# 1-B.net
KiCad netlist of a schematic drawn in EAGLE
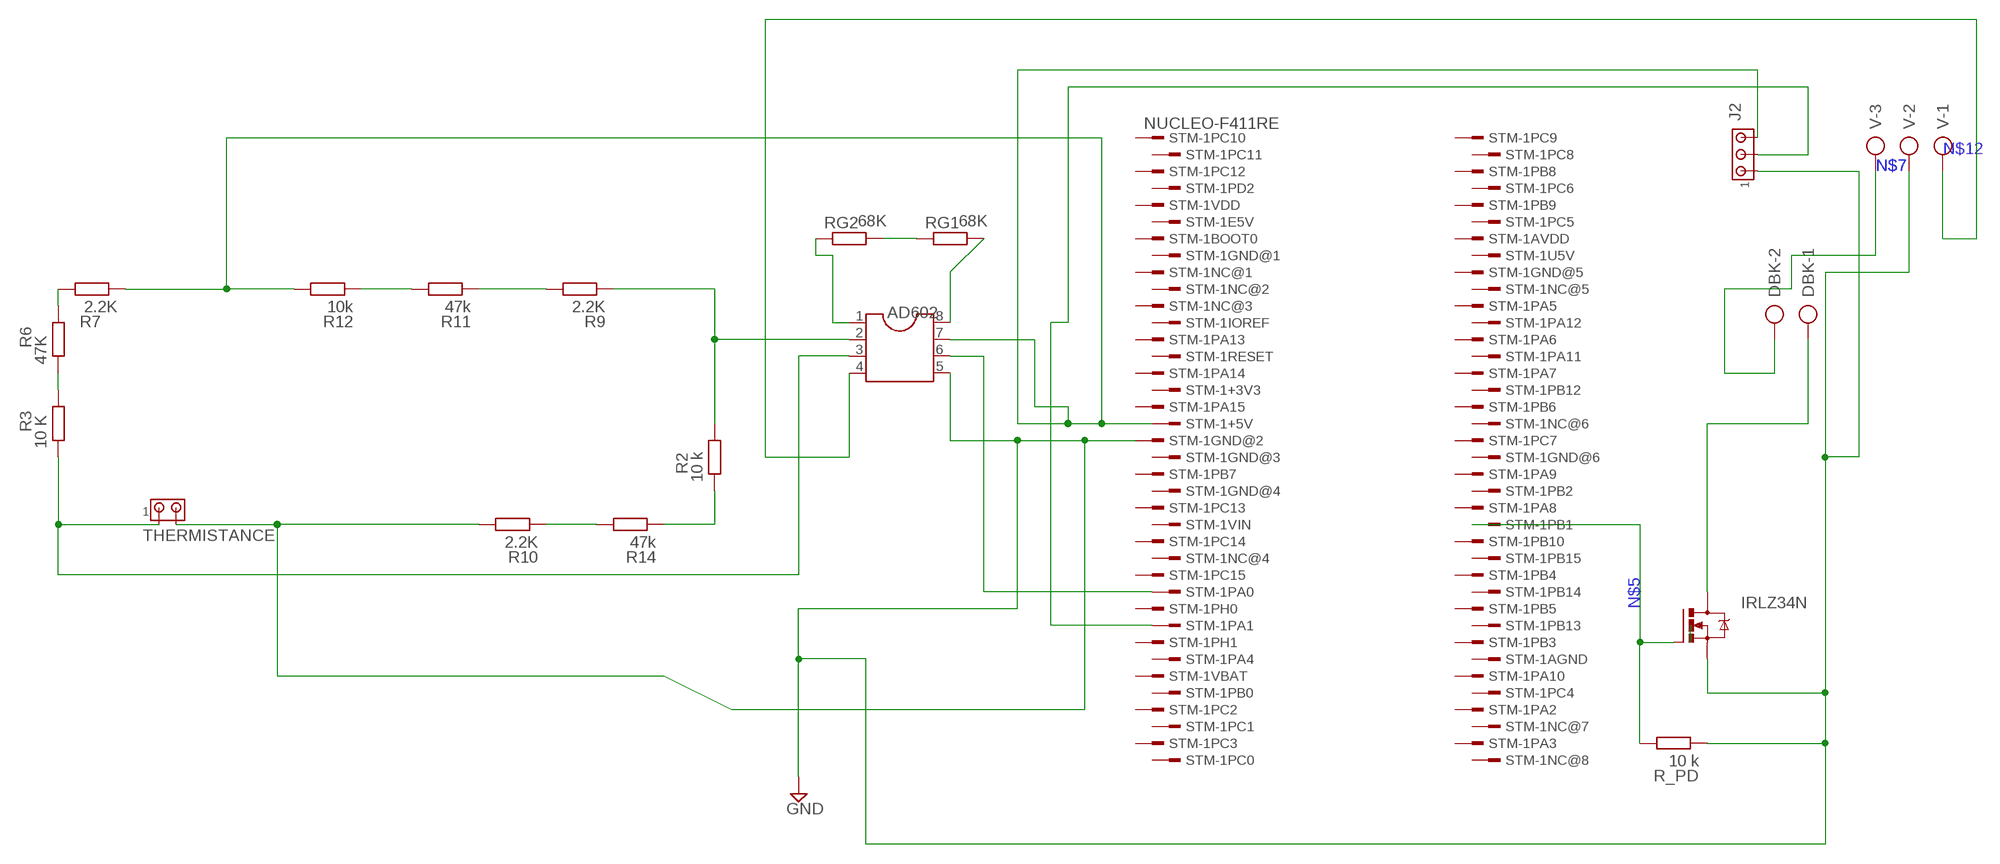
[diagram p0: schematic, sheet 1]

(export (version "E")
  (design (tool "Eeschema 10.0.6"))
  (components
    (comp (ref "AD602")
      (value "DIL8")
      (footprint "eagle-import:DIL08")
      (libsource (lib "eagle-import") (part "DIL8"))
    )
    (comp (ref "DBK")
      (value "AK500/2-H")
      (footprint "eagle-import:AK500_2-H")
      (libsource (lib "eagle-import") (part "AK500/2-H"))
    )
    (comp (ref "IRLZ34N")
      (value "IRLZ44Z")
      (footprint "eagle-import:TO220BH")
      (libsource (lib "eagle-import") (part "IRLZ44Z"))
    )
    (comp (ref "J2")
      (value "MTA03-100")
      (footprint "eagle-import:10X03MTA")
      (libsource (lib "eagle-import") (part "MTA03-100"))
    )
    (comp (ref "R2")
      (value "10 k")
      (footprint "eagle-import:0207_7")
      (libsource (lib "eagle-import") (part "R-EU_0207/7"))
    )
    (comp (ref "R3")
      (value "10 K")
      (footprint "eagle-import:0207_7")
      (libsource (lib "eagle-import") (part "R-EU_0207/7"))
    )
    (comp (ref "R6")
      (value "47K")
      (footprint "eagle-import:0207_7")
      (libsource (lib "eagle-import") (part "R-EU_0207/7"))
    )
    (comp (ref "R7")
      (value "2.2K")
      (footprint "eagle-import:0207_7")
      (libsource (lib "eagle-import") (part "R-EU_0207/7"))
    )
    (comp (ref "R9")
      (value "2.2K")
      (footprint "eagle-import:0207_7")
      (libsource (lib "eagle-import") (part "R-EU_0207/7"))
    )
    (comp (ref "R10")
      (value "2.2K")
      (footprint "eagle-import:0207_7")
      (libsource (lib "eagle-import") (part "R-EU_0207/7"))
    )
    (comp (ref "R11")
      (value "47k")
      (footprint "eagle-import:0207_7")
      (libsource (lib "eagle-import") (part "R-EU_0207/7"))
    )
    (comp (ref "R12")
      (value "10k")
      (footprint "eagle-import:0207_7")
      (libsource (lib "eagle-import") (part "R-EU_0207/7"))
    )
    (comp (ref "R14")
      (value "47k")
      (footprint "eagle-import:0207_7")
      (libsource (lib "eagle-import") (part "R-EU_0207/7"))
    )
    (comp (ref "RG1")
      (value "68K")
      (footprint "eagle-import:0207_7")
      (libsource (lib "eagle-import") (part "R-EU_0207/7"))
    )
    (comp (ref "RG2")
      (value "68K")
      (footprint "eagle-import:0207_7")
      (libsource (lib "eagle-import") (part "R-EU_0207/7"))
    )
    (comp (ref "R_PD")
      (value "10 k")
      (footprint "eagle-import:0207_7")
      (libsource (lib "eagle-import") (part "R-EU_0207/7"))
    )
    (comp (ref "STM-1")
      (value "NUCLEO-F411RE")
      (footprint "eagle-import:CONN_STM32_NUCLEO")
      (libsource (lib "eagle-import") (part "NUCLEO-F411RE"))
    )
    (comp (ref "THERMISTANCE")
      (value "MTA02-156")
      (footprint "eagle-import:1X2MTA")
      (libsource (lib "eagle-import") (part "MTA02-156"))
    )
    (comp (ref "V")
      (value "AK500/3-H")
      (footprint "eagle-import:AK500_3-H")
      (libsource (lib "eagle-import") (part "AK500/3-H"))
    )
  )
  (nets
    (net (code "1") (name "GND") (class "Default")
      (node (ref "AD602") (pin "5") (pinfunction "5_5") (pintype "passive"))
      (node (ref "IRLZ34N") (pin "S") (pinfunction "S_S") (pintype "passive"))
      (node (ref "J2") (pin "1") (pinfunction "1_1") (pintype "passive"))
      (node (ref "R10") (pin "2") (pinfunction "2_2") (pintype "passive"))
      (node (ref "R_PD") (pin "1") (pinfunction "1_1") (pintype "passive"))
      (node (ref "STM-1") (pin "19") (pinfunction "1_19") (pintype "passive"))
      (node (ref "THERMISTANCE") (pin "2") (pinfunction "2_2") (pintype "passive"))
      (node (ref "V") (pin "2") (pinfunction "KL_2") (pintype "passive"))
    )
    (net (code "2") (name "Net-(AD602-Pad1)") (class "Default")
      (node (ref "AD602") (pin "1") (pinfunction "1_1") (pintype "passive"))
      (node (ref "RG2") (pin "1") (pinfunction "1_1") (pintype "passive"))
    )
    (net (code "3") (name "Net-(AD602-Pad2)") (class "Default")
      (node (ref "AD602") (pin "2") (pinfunction "2_2") (pintype "passive"))
      (node (ref "R2") (pin "2") (pinfunction "2_2") (pintype "passive"))
      (node (ref "R9") (pin "1") (pinfunction "1_1") (pintype "passive"))
    )
    (net (code "4") (name "Net-(AD602-Pad3)") (class "Default")
      (node (ref "AD602") (pin "3") (pinfunction "3_3") (pintype "passive"))
      (node (ref "R3") (pin "1") (pinfunction "1_1") (pintype "passive"))
      (node (ref "THERMISTANCE") (pin "1") (pinfunction "1_1") (pintype "passive"))
    )
    (net (code "5") (name "Net-(AD602-Pad8)") (class "Default")
      (node (ref "AD602") (pin "8") (pinfunction "8_8") (pintype "passive"))
      (node (ref "RG1") (pin "2") (pinfunction "2_2") (pintype "passive"))
    )
    (net (code "6") (name "Net-(DBKA-KL)") (class "Default")
      (node (ref "DBK") (pin "1") (pinfunction "KL_1") (pintype "passive"))
      (node (ref "IRLZ34N") (pin "D") (pinfunction "D_D") (pintype "passive"))
    )
    (net (code "7") (name "Net-(DBKB-KL)") (class "Default")
      (node (ref "DBK") (pin "2") (pinfunction "KL_2") (pintype "passive"))
      (node (ref "V") (pin "3") (pinfunction "KL_3") (pintype "passive"))
    )
    (net (code "8") (name "Net-(R3-Pad2)") (class "Default")
      (node (ref "R3") (pin "2") (pinfunction "2_2") (pintype "passive"))
      (node (ref "R6") (pin "1") (pinfunction "1_1") (pintype "passive"))
    )
    (net (code "9") (name "Net-(R6-Pad2)") (class "Default")
      (node (ref "R6") (pin "2") (pinfunction "2_2") (pintype "passive"))
      (node (ref "R7") (pin "2") (pinfunction "2_2") (pintype "passive"))
    )
    (net (code "10") (name "Net-(R10-Pad1)") (class "Default")
      (node (ref "R10") (pin "1") (pinfunction "1_1") (pintype "passive"))
      (node (ref "R14") (pin "2") (pinfunction "2_2") (pintype "passive"))
    )
    (net (code "11") (name "Net-(R11-Pad1)") (class "Default")
      (node (ref "R11") (pin "1") (pinfunction "1_1") (pintype "passive"))
      (node (ref "R9") (pin "2") (pinfunction "2_2") (pintype "passive"))
    )
    (net (code "12") (name "Net-(R11-Pad2)") (class "Default")
      (node (ref "R11") (pin "2") (pinfunction "2_2") (pintype "passive"))
      (node (ref "R12") (pin "1") (pinfunction "1_1") (pintype "passive"))
    )
    (net (code "13") (name "Net-(R14-Pad1)") (class "Default")
      (node (ref "R14") (pin "1") (pinfunction "1_1") (pintype "passive"))
      (node (ref "R2") (pin "1") (pinfunction "1_1") (pintype "passive"))
    )
    (net (code "14") (name "Net-(RG1-Pad1)") (class "Default")
      (node (ref "RG1") (pin "1") (pinfunction "1_1") (pintype "passive"))
      (node (ref "RG2") (pin "2") (pinfunction "2_2") (pintype "passive"))
    )
    (net (code "15") (name "Net-(STM-1AM-1)") (class "Default")
      (node (ref "IRLZ34N") (pin "G") (pinfunction "G_G") (pintype "passive"))
      (node (ref "R_PD") (pin "2") (pinfunction "2_2") (pintype "passive"))
      (node (ref "STM-1") (pin "62") (pinfunction "1_62") (pintype "passive"))
    )
    (net (code "16") (name "Net-(STM-1B-1)") (class "Default")
      (node (ref "AD602") (pin "7") (pinfunction "7_7") (pintype "passive"))
      (node (ref "J2") (pin "3") (pinfunction "3_3") (pintype "passive"))
      (node (ref "R12") (pin "2") (pinfunction "2_2") (pintype "passive"))
      (node (ref "R7") (pin "1") (pinfunction "1_1") (pintype "passive"))
      (node (ref "STM-1") (pin "18") (pinfunction "1_18") (pintype "passive"))
    )
    (net (code "17") (name "Net-(STM-1V-1)") (class "Default")
      (node (ref "AD602") (pin "6") (pinfunction "6_6") (pintype "passive"))
      (node (ref "STM-1") (pin "28") (pinfunction "1_28") (pintype "passive"))
    )
    (net (code "18") (name "Net-(STM-1W-1)") (class "Default")
      (node (ref "J2") (pin "2") (pinfunction "2_2") (pintype "passive"))
      (node (ref "STM-1") (pin "30") (pinfunction "1_30") (pintype "passive"))
    )
    (net (code "19") (name "Net-(VA-KL)") (class "Default")
      (node (ref "AD602") (pin "4") (pinfunction "4_4") (pintype "passive"))
      (node (ref "V") (pin "1") (pinfunction "KL_1") (pintype "passive"))
    )
    (net (code "20") (name "unconnected-(STM-1-Pad1)") (class "Default")
      (node (ref "STM-1") (pin "1") (pinfunction "1_1") (pintype "passive"))
    )
    (net (code "21") (name "unconnected-(STM-1A-1-Pad16)") (class "Default")
      (node (ref "STM-1") (pin "16") (pinfunction "1_16") (pintype "passive"))
    )
    (net (code "22") (name "unconnected-(STM-1AA-1-Pad13)") (class "Default")
      (node (ref "STM-1") (pin "13") (pinfunction "1_13") (pintype "passive"))
    )
    (net (code "23") (name "unconnected-(STM-1AB-1-Pad15)") (class "Default")
      (node (ref "STM-1") (pin "15") (pinfunction "1_15") (pintype "passive"))
    )
    (net (code "24") (name "unconnected-(STM-1AC-1-Pad17)") (class "Default")
      (node (ref "STM-1") (pin "17") (pinfunction "1_17") (pintype "passive"))
    )
    (net (code "25") (name "unconnected-(STM-1AD-1-Pad73)") (class "Default")
      (node (ref "STM-1") (pin "73") (pinfunction "1_73") (pintype "passive"))
    )
    (net (code "26") (name "unconnected-(STM-1AE-1-Pad75)") (class "Default")
      (node (ref "STM-1") (pin "75") (pinfunction "1_75") (pintype "passive"))
    )
    (net (code "27") (name "unconnected-(STM-1AF-1-Pad32)") (class "Default")
      (node (ref "STM-1") (pin "32") (pinfunction "1_32") (pintype "passive"))
    )
    (net (code "28") (name "unconnected-(STM-1AG-1-Pad49)") (class "Default")
      (node (ref "STM-1") (pin "49") (pinfunction "1_49") (pintype "passive"))
    )
    (net (code "29") (name "unconnected-(STM-1AH-1-Pad51)") (class "Default")
      (node (ref "STM-1") (pin "51") (pinfunction "1_51") (pintype "passive"))
    )
    (net (code "30") (name "unconnected-(STM-1AI-1-Pad53)") (class "Default")
      (node (ref "STM-1") (pin "53") (pinfunction "1_53") (pintype "passive"))
    )
    (net (code "31") (name "unconnected-(STM-1AJ-1-Pad61)") (class "Default")
      (node (ref "STM-1") (pin "61") (pinfunction "1_61") (pintype "passive"))
    )
    (net (code "32") (name "unconnected-(STM-1AK-1-Pad59)") (class "Default")
      (node (ref "STM-1") (pin "59") (pinfunction "1_59") (pintype "passive"))
    )
    (net (code "33") (name "unconnected-(STM-1AL-1-Pad34)") (class "Default")
      (node (ref "STM-1") (pin "34") (pinfunction "1_34") (pintype "passive"))
    )
    (net (code "34") (name "unconnected-(STM-1AN-1-Pad63)") (class "Default")
      (node (ref "STM-1") (pin "63") (pinfunction "1_63") (pintype "passive"))
    )
    (net (code "35") (name "unconnected-(STM-1AO-1-Pad54)") (class "Default")
      (node (ref "STM-1") (pin "54") (pinfunction "1_54") (pintype "passive"))
    )
    (net (code "36") (name "unconnected-(STM-1AP-1-Pad68)") (class "Default")
      (node (ref "STM-1") (pin "68") (pinfunction "1_68") (pintype "passive"))
    )
    (net (code "37") (name "unconnected-(STM-1AQ-1-Pad66)") (class "Default")
      (node (ref "STM-1") (pin "66") (pinfunction "1_66") (pintype "passive"))
    )
    (net (code "38") (name "unconnected-(STM-1AR-1-Pad64)") (class "Default")
      (node (ref "STM-1") (pin "64") (pinfunction "1_64") (pintype "passive"))
    )
    (net (code "39") (name "unconnected-(STM-1AS-1-Pad60)") (class "Default")
      (node (ref "STM-1") (pin "60") (pinfunction "1_60") (pintype "passive"))
    )
    (net (code "40") (name "unconnected-(STM-1AT-1-Pad69)") (class "Default")
      (node (ref "STM-1") (pin "69") (pinfunction "1_69") (pintype "passive"))
    )
    (net (code "41") (name "unconnected-(STM-1AU-1-Pad65)") (class "Default")
      (node (ref "STM-1") (pin "65") (pinfunction "1_65") (pintype "passive"))
    )
    (net (code "42") (name "unconnected-(STM-1AV-1-Pad67)") (class "Default")
      (node (ref "STM-1") (pin "67") (pinfunction "1_67") (pintype "passive"))
    )
    (net (code "43") (name "unconnected-(STM-1AW-1-Pad55)") (class "Default")
      (node (ref "STM-1") (pin "55") (pinfunction "1_55") (pintype "passive"))
    )
    (net (code "44") (name "unconnected-(STM-1AX-1-Pad21)") (class "Default")
      (node (ref "STM-1") (pin "21") (pinfunction "1_21") (pintype "passive"))
    )
    (net (code "45") (name "unconnected-(STM-1AY-1-Pad41)") (class "Default")
      (node (ref "STM-1") (pin "41") (pinfunction "1_41") (pintype "passive"))
    )
    (net (code "46") (name "unconnected-(STM-1AZ-1-Pad43)") (class "Default")
      (node (ref "STM-1") (pin "43") (pinfunction "1_43") (pintype "passive"))
    )
    (net (code "47") (name "unconnected-(STM-1BA-1-Pad38)") (class "Default")
      (node (ref "STM-1") (pin "38") (pinfunction "1_38") (pintype "passive"))
    )
    (net (code "48") (name "unconnected-(STM-1BB-1-Pad36)") (class "Default")
      (node (ref "STM-1") (pin "36") (pinfunction "1_36") (pintype "passive"))
    )
    (net (code "49") (name "unconnected-(STM-1BD-1-Pad2)") (class "Default")
      (node (ref "STM-1") (pin "2") (pinfunction "1_2") (pintype "passive"))
    )
    (net (code "50") (name "unconnected-(STM-1BE-1-Pad3)") (class "Default")
      (node (ref "STM-1") (pin "3") (pinfunction "1_3") (pintype "passive"))
    )
    (net (code "51") (name "unconnected-(STM-1BF-1-Pad23)") (class "Default")
      (node (ref "STM-1") (pin "23") (pinfunction "1_23") (pintype "passive"))
    )
    (net (code "52") (name "unconnected-(STM-1BG-1-Pad25)") (class "Default")
      (node (ref "STM-1") (pin "25") (pinfunction "1_25") (pintype "passive"))
    )
    (net (code "53") (name "unconnected-(STM-1BH-1-Pad27)") (class "Default")
      (node (ref "STM-1") (pin "27") (pinfunction "1_27") (pintype "passive"))
    )
    (net (code "54") (name "unconnected-(STM-1BI-1-Pad35)") (class "Default")
      (node (ref "STM-1") (pin "35") (pinfunction "1_35") (pintype "passive"))
    )
    (net (code "55") (name "unconnected-(STM-1BJ-1-Pad37)") (class "Default")
      (node (ref "STM-1") (pin "37") (pinfunction "1_37") (pintype "passive"))
    )
    (net (code "56") (name "unconnected-(STM-1BK-1-Pad72)") (class "Default")
      (node (ref "STM-1") (pin "72") (pinfunction "1_72") (pintype "passive"))
    )
    (net (code "57") (name "unconnected-(STM-1BL-1-Pad44)") (class "Default")
      (node (ref "STM-1") (pin "44") (pinfunction "1_44") (pintype "passive"))
    )
    (net (code "58") (name "unconnected-(STM-1BM-1-Pad42)") (class "Default")
      (node (ref "STM-1") (pin "42") (pinfunction "1_42") (pintype "passive"))
    )
    (net (code "59") (name "unconnected-(STM-1BN-1-Pad57)") (class "Default")
      (node (ref "STM-1") (pin "57") (pinfunction "1_57") (pintype "passive"))
    )
    (net (code "60") (name "unconnected-(STM-1BO-1-Pad40)") (class "Default")
      (node (ref "STM-1") (pin "40") (pinfunction "1_40") (pintype "passive"))
    )
    (net (code "61") (name "unconnected-(STM-1BP-1-Pad39)") (class "Default")
      (node (ref "STM-1") (pin "39") (pinfunction "1_39") (pintype "passive"))
    )
    (net (code "62") (name "unconnected-(STM-1BQ-1-Pad4)") (class "Default")
      (node (ref "STM-1") (pin "4") (pinfunction "1_4") (pintype "passive"))
    )
    (net (code "63") (name "unconnected-(STM-1BR-1-Pad29)") (class "Default")
      (node (ref "STM-1") (pin "29") (pinfunction "1_29") (pintype "passive"))
    )
    (net (code "64") (name "unconnected-(STM-1BS-1-Pad31)") (class "Default")
      (node (ref "STM-1") (pin "31") (pinfunction "1_31") (pintype "passive"))
    )
    (net (code "65") (name "unconnected-(STM-1BT-1-Pad14)") (class "Default")
      (node (ref "STM-1") (pin "14") (pinfunction "1_14") (pintype "passive"))
    )
    (net (code "66") (name "unconnected-(STM-1BU-1-Pad46)") (class "Default")
      (node (ref "STM-1") (pin "46") (pinfunction "1_46") (pintype "passive"))
    )
    (net (code "67") (name "unconnected-(STM-1BV-1-Pad33)") (class "Default")
      (node (ref "STM-1") (pin "33") (pinfunction "1_33") (pintype "passive"))
    )
    (net (code "68") (name "unconnected-(STM-1BW-1-Pad5)") (class "Default")
      (node (ref "STM-1") (pin "5") (pinfunction "1_5") (pintype "passive"))
    )
    (net (code "69") (name "unconnected-(STM-1BX-1-Pad24)") (class "Default")
      (node (ref "STM-1") (pin "24") (pinfunction "1_24") (pintype "passive"))
    )
    (net (code "70") (name "unconnected-(STM-1C-1-Pad70)") (class "Default")
      (node (ref "STM-1") (pin "70") (pinfunction "1_70") (pintype "passive"))
    )
    (net (code "71") (name "unconnected-(STM-1D-1-Pad45)") (class "Default")
      (node (ref "STM-1") (pin "45") (pinfunction "1_45") (pintype "passive"))
    )
    (net (code "72") (name "unconnected-(STM-1E-1-Pad7)") (class "Default")
      (node (ref "STM-1") (pin "7") (pinfunction "1_7") (pintype "passive"))
    )
    (net (code "73") (name "unconnected-(STM-1F-1-Pad6)") (class "Default")
      (node (ref "STM-1") (pin "6") (pinfunction "1_6") (pintype "passive"))
    )
    (net (code "74") (name "unconnected-(STM-1G-1-Pad8)") (class "Default")
      (node (ref "STM-1") (pin "8") (pinfunction "1_8") (pintype "passive"))
    )
    (net (code "75") (name "unconnected-(STM-1I-1-Pad20)") (class "Default")
      (node (ref "STM-1") (pin "20") (pinfunction "1_20") (pintype "passive"))
    )
    (net (code "76") (name "unconnected-(STM-1J-1-Pad22)") (class "Default")
      (node (ref "STM-1") (pin "22") (pinfunction "1_22") (pintype "passive"))
    )
    (net (code "77") (name "unconnected-(STM-1K-1-Pad47)") (class "Default")
      (node (ref "STM-1") (pin "47") (pinfunction "1_47") (pintype "passive"))
    )
    (net (code "78") (name "unconnected-(STM-1L-1-Pad58)") (class "Default")
      (node (ref "STM-1") (pin "58") (pinfunction "1_58") (pintype "passive"))
    )
    (net (code "79") (name "unconnected-(STM-1M-1-Pad12)") (class "Default")
      (node (ref "STM-1") (pin "12") (pinfunction "1_12") (pintype "passive"))
    )
    (net (code "80") (name "unconnected-(STM-1N-1-Pad9)") (class "Default")
      (node (ref "STM-1") (pin "9") (pinfunction "1_9") (pintype "passive"))
    )
    (net (code "81") (name "unconnected-(STM-1O-1-Pad10)") (class "Default")
      (node (ref "STM-1") (pin "10") (pinfunction "1_10") (pintype "passive"))
    )
    (net (code "82") (name "unconnected-(STM-1P-1-Pad11)") (class "Default")
      (node (ref "STM-1") (pin "11") (pinfunction "1_11") (pintype "passive"))
    )
    (net (code "83") (name "unconnected-(STM-1Q-1-Pad26)") (class "Default")
      (node (ref "STM-1") (pin "26") (pinfunction "1_26") (pintype "passive"))
    )
    (net (code "84") (name "unconnected-(STM-1R-1-Pad48)") (class "Default")
      (node (ref "STM-1") (pin "48") (pinfunction "1_48") (pintype "passive"))
    )
    (net (code "85") (name "unconnected-(STM-1S-1-Pad56)") (class "Default")
      (node (ref "STM-1") (pin "56") (pinfunction "1_56") (pintype "passive"))
    )
    (net (code "86") (name "unconnected-(STM-1T-1-Pad74)") (class "Default")
      (node (ref "STM-1") (pin "74") (pinfunction "1_74") (pintype "passive"))
    )
    (net (code "87") (name "unconnected-(STM-1U-1-Pad76)") (class "Default")
      (node (ref "STM-1") (pin "76") (pinfunction "1_76") (pintype "passive"))
    )
    (net (code "88") (name "unconnected-(STM-1X-1-Pad71)") (class "Default")
      (node (ref "STM-1") (pin "71") (pinfunction "1_71") (pintype "passive"))
    )
    (net (code "89") (name "unconnected-(STM-1Y-1-Pad52)") (class "Default")
      (node (ref "STM-1") (pin "52") (pinfunction "1_52") (pintype "passive"))
    )
    (net (code "90") (name "unconnected-(STM-1Z-1-Pad50)") (class "Default")
      (node (ref "STM-1") (pin "50") (pinfunction "1_50") (pintype "passive"))
    )
  )
)
